# -.net
KiCad netlist of a schematic drawn in Altium Designer
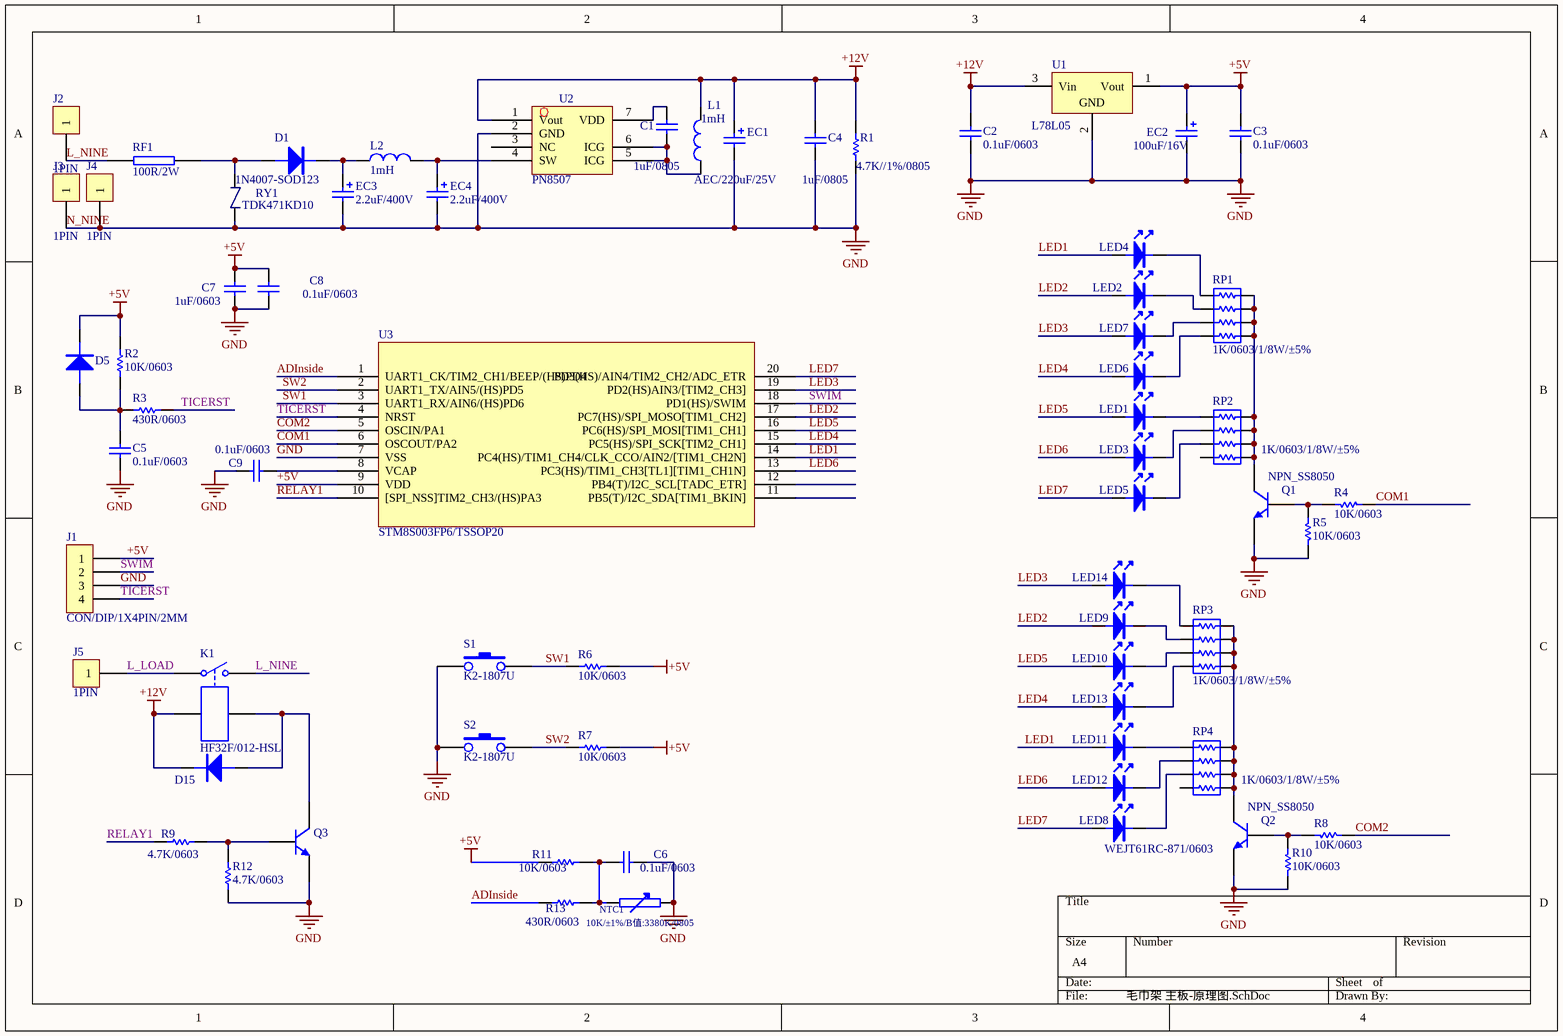
[diagram p0: 毛巾架 主板-原理图.SchDoc]

(export (version "E")
  (design (tool "Eeschema 10.0.6"))
  (components
    (comp (ref "C1")
      (value "1uF/0805")
      (footprint "CAP/SMT/0805C")
      (libsource (lib "Menred_原理图 封装库") (part "CAP/CAP/SMT/0805C"))
    )
    (comp (ref "C2")
      (value "0.1uF/0603")
      (footprint "CAP/SMT/0603C")
      (libsource (lib "Menred_原理图 封装库") (part "CAP/CAP/SMT/0603C"))
    )
    (comp (ref "C3")
      (value "0.1uF/0603")
      (footprint "CAP/SMT/0603C")
      (libsource (lib "Menred_原理图 封装库") (part "CAP/CAP/SMT/0603C"))
    )
    (comp (ref "C4")
      (value "1uF/0805")
      (footprint "CAP/SMT/0805C")
      (libsource (lib "Menred_原理图 封装库") (part "CAP/CAP/SMT/0805C"))
    )
    (comp (ref "C5")
      (value "0.1uF/0603")
      (footprint "CAP/SMT/0603C")
      (libsource (lib "Menred_原理图 封装库") (part "CAP/CAP/SMT/0603C"))
    )
    (comp (ref "C6")
      (value "0.1uF/0603")
      (footprint "CAP/SMT/0603C")
      (libsource (lib "Menred_原理图 封装库") (part "CAP/CAP/SMT/0603C"))
    )
    (comp (ref "C7")
      (value "1uF/0603")
      (footprint "CAP/SMT/0603C")
      (libsource (lib "Menred_原理图 封装库") (part "CAP/CAP/SMT/0603C"))
    )
    (comp (ref "C8")
      (value "0.1uF/0603")
      (footprint "CAP/SMT/0603C")
      (libsource (lib "Menred_原理图 封装库") (part "CAP/CAP/SMT/0603C"))
    )
    (comp (ref "C9")
      (value "0.1uF/0603")
      (footprint "CAP/SMT/0603C")
      (libsource (lib "Menred_原理图 封装库") (part "CAP/CAP/SMT/0603C"))
    )
    (comp (ref "D1")
      (value "1N4007-SOD123")
      (footprint "D/SMT/SOD123")
      (libsource (lib "二极管类器件") (part "D/D/SMT/1N4007-SOD123"))
    )
    (comp (ref "D5")
      (value "1N4148/SOD-123")
      (footprint "D/SMT/SOD-123")
      (description "VR=75V T(-65-175)P(0.5W)VF=0.6V")
      (libsource (lib "Menred_原理图 封装库") (part "D/D/SMT/1N4148/SOD-123"))
    )
    (comp (ref "D15")
      (value "1N4148/SOD-123")
      (footprint "D/SMT/SOD-123")
      (description "VR=75V T(-65-175)P(0.5W)VF=0.6V")
      (libsource (lib "Menred_原理图 封装库") (part "D/D/SMT/1N4148/SOD-123"))
    )
    (comp (ref "EC1")
      (value "AEC/220uF/25V")
      (footprint "CAP/DIP/330UF/25V")
      (libsource (lib "Menred_原理图 封装库") (part "CAP/AEC/DIP/330uF/25V"))
    )
    (comp (ref "EC2")
      (value "100uF/16V")
      (footprint "CAP/SMT/47uF/16V")
      (libsource (lib "Menred_原理图 封装库") (part "CAP/AEC/SMT/47uF/16V"))
    )
    (comp (ref "EC3")
      (value "2.2uF/400V")
      (footprint "CAP/DIP/2.2UF/400V/2.5mm")
      (libsource (lib "Menred_原理图 封装库") (part "CAP/AEC/DIP/2.2uF/400V"))
    )
    (comp (ref "EC4")
      (value "2.2uF/400V")
      (footprint "CAP/DIP/2.2UF/400V/2.5mm")
      (libsource (lib "Menred_原理图 封装库") (part "CAP/AEC/DIP/2.2uF/400V"))
    )
    (comp (ref "J1")
      (value "CON/DIP/1X4PIN/2MM")
      (footprint "CON/DIP/1×4PIN/2.0MM")
      (description "Connector")
      (libsource (lib "Menred_原理图 封装库") (part "CON/DIP/1X4PIN/2MM"))
    )
    (comp (ref "J2")
      (value "1PIN")
      (footprint "CON/DIP/1PIN")
      (description "Connector")
      (libsource (lib "Menred_原理图 封装库") (part "CON/DIP/1PIN"))
    )
    (comp (ref "J3")
      (value "1PIN")
      (footprint "CON/DIP/1PIN")
      (description "Connector")
      (libsource (lib "Menred_原理图 封装库") (part "CON/DIP/1PIN"))
    )
    (comp (ref "J4")
      (value "1PIN")
      (footprint "CON/DIP/1PIN")
      (description "Connector")
      (libsource (lib "Menred_原理图 封装库") (part "CON/DIP/1PIN"))
    )
    (comp (ref "J5")
      (value "1PIN")
      (footprint "CON/DIP/1PIN")
      (description "Connector")
      (libsource (lib "") (part "CON/DIP/1PIN_1"))
    )
    (comp (ref "K1")
      (value "HF32F/012-HSL")
      (footprint "RELAY/HF32F-012-HSL")
      (libsource (lib "Menred_原理图 封装库") (part "RELAY/GENERAL/DIP/HF32F/012-HSL"))
    )
    (comp (ref "L1")
      (value "1mH")
      (footprint "L/DIP/1mH")
      (description "工字电感")
      (libsource (lib "Menred_原理图 封装库") (part "L/L/DIP/JYGX68-1.0mH/300mA"))
    )
    (comp (ref "L2")
      (value "1mH")
      (footprint "L/DIP/1mH")
      (description "工字电感")
      (libsource (lib "Menred_原理图 封装库") (part "L/L/DIP/JYGX68-1.0mH/300mA"))
    )
    (comp (ref "LED1")
      (value "WEJT61RC-871/0603")
      (footprint "D/SMT/LED/0603")
      (libsource (lib "Menred_原理图 封装库") (part "D/LED/SMT/WEJT61RC-871/0603"))
    )
    (comp (ref "LED2")
      (value "WEJT61RC-871/0603")
      (footprint "D/SMT/LED/0603")
      (libsource (lib "Menred_原理图 封装库") (part "D/LED/SMT/WEJT61RC-871/0603"))
    )
    (comp (ref "LED3")
      (value "WEJT61RC-871/0603")
      (footprint "D/SMT/LED/0603")
      (libsource (lib "Menred_原理图 封装库") (part "D/LED/SMT/WEJT61RC-871/0603"))
    )
    (comp (ref "LED4")
      (value "WEJT61RC-871/0603")
      (footprint "D/SMT/LED/0603")
      (libsource (lib "Menred_原理图 封装库") (part "D/LED/SMT/WEJT61RC-871/0603"))
    )
    (comp (ref "LED5")
      (value "WEJT61RC-871/0603")
      (footprint "D/SMT/LED/0603")
      (libsource (lib "Menred_原理图 封装库") (part "D/LED/SMT/WEJT61RC-871/0603"))
    )
    (comp (ref "LED6")
      (value "WEJT61RC-871/0603")
      (footprint "D/SMT/LED/0603")
      (libsource (lib "Menred_原理图 封装库") (part "D/LED/SMT/WEJT61RC-871/0603"))
    )
    (comp (ref "LED7")
      (value "WEJT61RC-871/0603")
      (footprint "D/SMT/LED/0603")
      (libsource (lib "Menred_原理图 封装库") (part "D/LED/SMT/WEJT61RC-871/0603"))
    )
    (comp (ref "LED8")
      (value "WEJT61RC-871/0603")
      (footprint "D/SMT/LED/0603")
      (libsource (lib "Menred_原理图 封装库") (part "D/LED/SMT/WEJT61RC-871/0603"))
    )
    (comp (ref "LED9")
      (value "WEJT61RC-871/0603")
      (footprint "D/SMT/LED/0603")
      (libsource (lib "Menred_原理图 封装库") (part "D/LED/SMT/WEJT61RC-871/0603"))
    )
    (comp (ref "LED10")
      (value "WEJT61RC-871/0603")
      (footprint "D/SMT/LED/0603")
      (libsource (lib "Menred_原理图 封装库") (part "D/LED/SMT/WEJT61RC-871/0603"))
    )
    (comp (ref "LED11")
      (value "WEJT61RC-871/0603")
      (footprint "D/SMT/LED/0603")
      (libsource (lib "Menred_原理图 封装库") (part "D/LED/SMT/WEJT61RC-871/0603"))
    )
    (comp (ref "LED12")
      (value "WEJT61RC-871/0603")
      (footprint "D/SMT/LED/0603")
      (libsource (lib "Menred_原理图 封装库") (part "D/LED/SMT/WEJT61RC-871/0603"))
    )
    (comp (ref "LED13")
      (value "WEJT61RC-871/0603")
      (footprint "D/SMT/LED/0603")
      (libsource (lib "Menred_原理图 封装库") (part "D/LED/SMT/WEJT61RC-871/0603"))
    )
    (comp (ref "LED14")
      (value "WEJT61RC-871/0603")
      (footprint "D/SMT/LED/0603")
      (libsource (lib "Menred_原理图 封装库") (part "D/LED/SMT/WEJT61RC-871/0603"))
    )
    (comp (ref "NTC1")
      (value "10K/±1%/B值:3380K/0805")
      (footprint "Sensor/S_NTC_DIP")
      (description "3380(10K)")
      (libsource (lib "Menred_原理图 封装库") (part "SENSOR/NTC_SMD"))
    )
    (comp (ref "Q1")
      (value "NPN_SS8050")
      (footprint "BJT/SMT/SOT-23")
      (description "Vce25V/Vcb40V/Veb5V/Ic1.5V/Pd300mW")
      (fields (field (name "PUBLISHER") "*"))
      (libsource (lib "Menred_原理图 封装库") (part "BJT/NPN/SMT/SS8050/SOT-23"))
    )
    (comp (ref "Q2")
      (value "NPN_SS8050")
      (footprint "BJT/SMT/SOT-23")
      (description "Vce25V/Vcb40V/Veb5V/Ic1.5V/Pd300mW")
      (fields (field (name "PUBLISHER") "*"))
      (libsource (lib "Menred_原理图 封装库") (part "BJT/NPN/SMT/SS8050/SOT-23"))
    )
    (comp (ref "Q3")
      (value "NPN_SS8050")
      (footprint "BJT/SMT/SOT-23")
      (fields (field (name "PUBLISHER") "*"))
      (libsource (lib "Menred_原理图 封装库") (part "BJT/NPN/SMT/SS8050/SOT-23"))
    )
    (comp (ref "R1")
      (value "4.7K//1%/0805")
      (footprint "0805R")
      (libsource (lib "Menred_原理图 封装库") (part "RES/RES/SMT/0805"))
    )
    (comp (ref "R2")
      (value "10K/0603")
      (footprint "0603R")
      (libsource (lib "Menred_原理图 封装库") (part "RES/RES/SMT/0603"))
    )
    (comp (ref "R3")
      (value "430R/0603")
      (footprint "0603R")
      (libsource (lib "Menred_原理图 封装库") (part "RES/RES/SMT/0603"))
    )
    (comp (ref "R4")
      (value "10K/0603")
      (footprint "0603R")
      (libsource (lib "Menred_原理图 封装库") (part "RES/RES/SMT/0603"))
    )
    (comp (ref "R5")
      (value "10K/0603")
      (footprint "0603R")
      (libsource (lib "Menred_原理图 封装库") (part "RES/RES/SMT/0603"))
    )
    (comp (ref "R6")
      (value "10K/0603")
      (footprint "0603R")
      (libsource (lib "Menred_原理图 封装库") (part "RES/RES/SMT/0603"))
    )
    (comp (ref "R7")
      (value "10K/0603")
      (footprint "0603R")
      (libsource (lib "Menred_原理图 封装库") (part "RES/RES/SMT/0603"))
    )
    (comp (ref "R8")
      (value "10K/0603")
      (footprint "0603R")
      (libsource (lib "Menred_原理图 封装库") (part "RES/RES/SMT/0603"))
    )
    (comp (ref "R9")
      (value "4.7K/0603")
      (footprint "0603R")
      (libsource (lib "Menred_原理图 封装库") (part "RES/RES/SMT/0603"))
    )
    (comp (ref "R10")
      (value "10K/0603")
      (footprint "0603R")
      (libsource (lib "Menred_原理图 封装库") (part "RES/RES/SMT/0603"))
    )
    (comp (ref "R11")
      (value "10K/0603")
      (footprint "0603R")
      (libsource (lib "Menred_原理图 封装库") (part "RES/RES/SMT/0603"))
    )
    (comp (ref "R12")
      (value "4.7K/0603")
      (footprint "0603R")
      (libsource (lib "Menred_原理图 封装库") (part "RES/RES/SMT/0603"))
    )
    (comp (ref "R13")
      (value "430R/0603")
      (footprint "0603R")
      (libsource (lib "Menred_原理图 封装库") (part "RES/RES/SMT/0603"))
    )
    (comp (ref "RF1")
      (value "100R/2W")
      (footprint "FUSE/3.15A")
      (libsource (lib "Menred_原理图 封装库") (part "FUSE/FUSE/DIP/3.15A"))
    )
    (comp (ref "RP1")
      (value "1K/0603/1/8W/±5%")
      (footprint "0603R*4")
      (description "Isolated Resistor Network")
      (fields (field (name "PUBLISHER") "Altium Limited"))
      (libsource (lib "Menred_原理图 封装库") (part "RES /PACKS/SMT/0603*4"))
    )
    (comp (ref "RP2")
      (value "1K/0603/1/8W/±5%")
      (footprint "0603R*4")
      (description "Isolated Resistor Network")
      (fields (field (name "PUBLISHER") "Altium Limited"))
      (libsource (lib "Menred_原理图 封装库") (part "RES /PACKS/SMT/0603*4"))
    )
    (comp (ref "RP3")
      (value "1K/0603/1/8W/±5%")
      (footprint "0603R*4")
      (description "Isolated Resistor Network")
      (fields (field (name "PUBLISHER") "Altium Limited"))
      (libsource (lib "Menred_原理图 封装库") (part "RES /PACKS/SMT/0603*4"))
    )
    (comp (ref "RP4")
      (value "1K/0603/1/8W/±5%")
      (footprint "0603R*4")
      (description "Isolated Resistor Network")
      (fields (field (name "PUBLISHER") "Altium Limited"))
      (libsource (lib "Menred_原理图 封装库") (part "RES /PACKS/SMT/0603*4"))
    )
    (comp (ref "RY1")
      (value "TDK471KD10")
      (footprint "RES/RY/TDK471KD10")
      (libsource (lib "Menred_原理图 封装库") (part "RES/RY/DIP/TDK471KD10"))
    )
    (comp (ref "S1")
      (value "K2-1807U")
      (footprint "SWITCH/K2-1807U")
      (libsource (lib "Menred_原理图 封装库") (part "SWITCH/SMT/K2-1807U"))
    )
    (comp (ref "S2")
      (value "K2-1807U")
      (footprint "SWITCH/K2-1807U")
      (libsource (lib "Menred_原理图 封装库") (part "SWITCH/SMT/K2-1807U"))
    )
    (comp (ref "U1")
      (value "L78L05")
      (footprint "SOT-89-3L(78L05)")
      (description "5V三端稳压器 output imax 0.1A")
      (fields (field (name "MANUFACTURER") "Generic Components"))
      (libsource (lib "Menred_原理图 封装库") (part "IC/POWER/SMT/L78L05/SOT-89"))
    )
    (comp (ref "U2")
      (value "PN8507")
      (footprint "SOP-7")
      (libsource (lib "集成芯片类") (part "IC/POWER/SMT/PN8507/SOP-8"))
    )
    (comp (ref "U3")
      (value "STM8S003FP6/TSSOP20")
      (footprint "TSSOP20")
      (libsource (lib "Menred_原理图 封装库") (part "MCU/SMT/STM8S003FP6/TSSOP20"))
    )
  )
  (nets
    (net (code "1") (name "+5V") (class "Default")
      (node (ref "C3") (pin "2") (pinfunction "2_2") (pintype "passive"))
      (node (ref "C7") (pin "2") (pinfunction "2_2") (pintype "passive"))
      (node (ref "C8") (pin "2") (pinfunction "2_2") (pintype "passive"))
      (node (ref "D5") (pin "1") (pinfunction "K_1") (pintype "passive"))
      (node (ref "EC2") (pin "1") (pinfunction "1_1") (pintype "passive"))
      (node (ref "J1") (pin "1") (pinfunction "1_1") (pintype "passive"))
      (node (ref "R11") (pin "2") (pinfunction "2_2") (pintype "passive"))
      (node (ref "R2") (pin "1") (pinfunction "1_1") (pintype "passive"))
      (node (ref "R6") (pin "2") (pinfunction "2_2") (pintype "passive"))
      (node (ref "R7") (pin "2") (pinfunction "2_2") (pintype "passive"))
      (node (ref "U1") (pin "1") (pinfunction "Vout_1") (pintype "passive"))
      (node (ref "U3") (pin "9") (pinfunction "VDD_9") (pintype "power_in"))
    )
    (net (code "2") (name "+12V") (class "Default")
      (node (ref "C2") (pin "2") (pinfunction "2_2") (pintype "passive"))
      (node (ref "C4") (pin "2") (pinfunction "2_2") (pintype "passive"))
      (node (ref "D15") (pin "1") (pinfunction "K_1") (pintype "passive"))
      (node (ref "EC1") (pin "1") (pinfunction "1_1") (pintype "passive"))
      (node (ref "K1") (pin "3") (pinfunction "3_3") (pintype "passive"))
      (node (ref "L1") (pin "2") (pinfunction "2_2") (pintype "passive"))
      (node (ref "R1") (pin "2") (pinfunction "2_2") (pintype "passive"))
      (node (ref "U1") (pin "3") (pinfunction "Vin_3") (pintype "passive"))
      (node (ref "U2") (pin "1") (pinfunction "Vout_1") (pintype "passive"))
    )
    (net (code "3") (name "/ADInside") (class "Default")
      (node (ref "R13") (pin "2") (pinfunction "2_2") (pintype "passive"))
      (node (ref "U3") (pin "1") (pinfunction "UART1_CK/TIM2_CH1/BEEP/(HS)PD4_1") (pintype "power_in"))
    )
    (net (code "4") (name "/COM1") (class "Default")
      (node (ref "R4") (pin "1") (pinfunction "1_1") (pintype "passive"))
      (node (ref "U3") (pin "6") (pinfunction "OSCOUT/PA2_6") (pintype "power_in"))
    )
    (net (code "5") (name "/COM2") (class "Default")
      (node (ref "R8") (pin "1") (pinfunction "1_1") (pintype "passive"))
      (node (ref "U3") (pin "5") (pinfunction "OSCIN/PA1_5") (pintype "power_in"))
    )
    (net (code "6") (name "/LED1") (class "Default")
      (node (ref "LED11") (pin "2") (pinfunction "A_2") (pintype "passive"))
      (node (ref "LED4") (pin "2") (pinfunction "A_2") (pintype "passive"))
      (node (ref "U3") (pin "14") (pinfunction "PC4(HS)/TIM1_CH4/CLK_CCO/AIN2/[TIM1_CH2N]_14") (pintype "power_in"))
    )
    (net (code "7") (name "/LED2") (class "Default")
      (node (ref "LED2") (pin "2") (pinfunction "A_2") (pintype "passive"))
      (node (ref "LED9") (pin "2") (pinfunction "A_2") (pintype "passive"))
      (node (ref "U3") (pin "17") (pinfunction "PC7(HS)/SPI_MOSO[TIM1_CH2]_17") (pintype "power_in"))
    )
    (net (code "8") (name "/LED3") (class "Default")
      (node (ref "LED14") (pin "2") (pinfunction "A_2") (pintype "passive"))
      (node (ref "LED7") (pin "2") (pinfunction "A_2") (pintype "passive"))
      (node (ref "U3") (pin "19") (pinfunction "PD2(HS)AIN3/[TIM2_CH3]_19") (pintype "power_in"))
    )
    (net (code "9") (name "/LED4") (class "Default")
      (node (ref "LED13") (pin "2") (pinfunction "A_2") (pintype "passive"))
      (node (ref "LED6") (pin "2") (pinfunction "A_2") (pintype "passive"))
      (node (ref "U3") (pin "15") (pinfunction "PC5(HS)/SPI_SCK[TIM2_CH1]_15") (pintype "power_in"))
    )
    (net (code "10") (name "/LED5") (class "Default")
      (node (ref "LED1") (pin "2") (pinfunction "A_2") (pintype "passive"))
      (node (ref "LED10") (pin "2") (pinfunction "A_2") (pintype "passive"))
      (node (ref "U3") (pin "16") (pinfunction "PC6(HS)/SPI_MOSI[TIM1_CH1]_16") (pintype "power_in"))
    )
    (net (code "11") (name "/LED6") (class "Default")
      (node (ref "LED12") (pin "2") (pinfunction "A_2") (pintype "passive"))
      (node (ref "LED3") (pin "2") (pinfunction "A_2") (pintype "passive"))
      (node (ref "U3") (pin "13") (pinfunction "PC3(HS)/TIM1_CH3[TL1][TIM1_CH1N]_13") (pintype "power_in"))
    )
    (net (code "12") (name "/LED7") (class "Default")
      (node (ref "LED5") (pin "2") (pinfunction "A_2") (pintype "passive"))
      (node (ref "LED8") (pin "2") (pinfunction "A_2") (pintype "passive"))
      (node (ref "U3") (pin "20") (pinfunction "PD3(HS)/AIN4/TIM2_CH2/ADC_ETR_20") (pintype "power_in"))
    )
    (net (code "13") (name "/L_LOAD") (class "Default")
      (node (ref "J5") (pin "1") (pinfunction "1_1") (pintype "passive"))
      (node (ref "K1") (pin "1") (pinfunction "1_1") (pintype "passive"))
    )
    (net (code "14") (name "/L_NINE") (class "Default")
      (node (ref "J2") (pin "1") (pinfunction "1_1") (pintype "passive"))
      (node (ref "K1") (pin "2") (pinfunction "2_2") (pintype "passive"))
      (node (ref "RF1") (pin "2") (pinfunction "2_2") (pintype "passive"))
    )
    (net (code "15") (name "/RELAY1") (class "Default")
      (node (ref "R9") (pin "2") (pinfunction "2_2") (pintype "passive"))
      (node (ref "U3") (pin "10") (pinfunction "[SPI_NSS]TIM2_CH3/(HS)PA3_10") (pintype "power_in"))
    )
    (net (code "16") (name "/SW1") (class "Default")
      (node (ref "R6") (pin "1") (pinfunction "1_1") (pintype "passive"))
      (node (ref "S1") (pin "2") (pinfunction "2_2") (pintype "passive"))
      (node (ref "U3") (pin "3") (pinfunction "UART1_RX/AIN6/(HS)PD6_3") (pintype "power_in"))
    )
    (net (code "17") (name "/SW2") (class "Default")
      (node (ref "R7") (pin "1") (pinfunction "1_1") (pintype "passive"))
      (node (ref "S2") (pin "2") (pinfunction "2_2") (pintype "passive"))
      (node (ref "U3") (pin "2") (pinfunction "UART1_TX/AIN5/(HS)PD5_2") (pintype "power_in"))
    )
    (net (code "18") (name "/SWIM") (class "Default")
      (node (ref "J1") (pin "2") (pinfunction "2_2") (pintype "passive"))
      (node (ref "U3") (pin "18") (pinfunction "PD1(HS)/SWIM_18") (pintype "power_in"))
    )
    (net (code "19") (name "/TICERST") (class "Default")
      (node (ref "J1") (pin "4") (pinfunction "4_4") (pintype "passive"))
      (node (ref "R3") (pin "2") (pinfunction "2_2") (pintype "passive"))
      (node (ref "U3") (pin "4") (pinfunction "NRST_4") (pintype "power_in"))
    )
    (net (code "20") (name "GND") (class "Default")
      (node (ref "C2") (pin "1") (pinfunction "1_1") (pintype "passive"))
      (node (ref "C3") (pin "1") (pinfunction "1_1") (pintype "passive"))
      (node (ref "C4") (pin "1") (pinfunction "1_1") (pintype "passive"))
      (node (ref "C5") (pin "2") (pinfunction "2_2") (pintype "passive"))
      (node (ref "C6") (pin "1") (pinfunction "1_1") (pintype "passive"))
      (node (ref "C7") (pin "1") (pinfunction "1_1") (pintype "passive"))
      (node (ref "C8") (pin "1") (pinfunction "1_1") (pintype "passive"))
      (node (ref "C9") (pin "2") (pinfunction "2_2") (pintype "passive"))
      (node (ref "EC1") (pin "2") (pinfunction "2_2") (pintype "passive"))
      (node (ref "EC2") (pin "2") (pinfunction "2_2") (pintype "passive"))
      (node (ref "EC3") (pin "2") (pinfunction "2_2") (pintype "passive"))
      (node (ref "EC4") (pin "2") (pinfunction "2_2") (pintype "passive"))
      (node (ref "J1") (pin "3") (pinfunction "3_3") (pintype "passive"))
      (node (ref "J3") (pin "1") (pinfunction "1_1") (pintype "passive"))
      (node (ref "J4") (pin "1") (pinfunction "1_1") (pintype "passive"))
      (node (ref "NTC1") (pin "2") (pinfunction "2_2") (pintype "passive"))
      (node (ref "Q1") (pin "2") (pinfunction "E_2") (pintype "passive"))
      (node (ref "Q2") (pin "2") (pinfunction "E_2") (pintype "passive"))
      (node (ref "Q3") (pin "2") (pinfunction "E_2") (pintype "passive"))
      (node (ref "R1") (pin "1") (pinfunction "1_1") (pintype "passive"))
      (node (ref "R10") (pin "2") (pinfunction "2_2") (pintype "passive"))
      (node (ref "R12") (pin "2") (pinfunction "2_2") (pintype "passive"))
      (node (ref "R5") (pin "2") (pinfunction "2_2") (pintype "passive"))
      (node (ref "RY1") (pin "1") (pinfunction "1_1") (pintype "passive"))
      (node (ref "S1") (pin "1") (pinfunction "1_1") (pintype "passive"))
      (node (ref "S2") (pin "1") (pinfunction "1_1") (pintype "passive"))
      (node (ref "U1") (pin "2") (pinfunction "GND_2") (pintype "passive"))
      (node (ref "U2") (pin "2") (pinfunction "GND_2") (pintype "passive"))
      (node (ref "U3") (pin "7") (pinfunction "VSS_7") (pintype "power_in"))
    )
    (net (code "21") (name "Net-(C1-Pad1)") (class "Default")
      (node (ref "C1") (pin "1") (pinfunction "1_1") (pintype "passive"))
      (node (ref "L1") (pin "1") (pinfunction "1_1") (pintype "passive"))
      (node (ref "U2") (pin "5") (pinfunction "ICG_5") (pintype "passive"))
      (node (ref "U2") (pin "6") (pinfunction "ICG_6") (pintype "passive"))
    )
    (net (code "22") (name "Net-(C6-Pad2)") (class "Default")
      (node (ref "C6") (pin "2") (pinfunction "2_2") (pintype "passive"))
      (node (ref "NTC1") (pin "1") (pinfunction "1_1") (pintype "passive"))
      (node (ref "R11") (pin "1") (pinfunction "1_1") (pintype "passive"))
      (node (ref "R13") (pin "1") (pinfunction "1_1") (pintype "passive"))
    )
    (net (code "23") (name "Net-(D1-A)") (class "Default")
      (node (ref "D1") (pin "2") (pinfunction "A_2") (pintype "passive"))
      (node (ref "RF1") (pin "1") (pinfunction "1_1") (pintype "passive"))
      (node (ref "RY1") (pin "2") (pinfunction "2_2") (pintype "passive"))
    )
    (net (code "24") (name "Net-(D1-K)") (class "Default")
      (node (ref "D1") (pin "1") (pinfunction "K_1") (pintype "passive"))
      (node (ref "EC3") (pin "1") (pinfunction "1_1") (pintype "passive"))
      (node (ref "L2") (pin "1") (pinfunction "1_1") (pintype "passive"))
    )
    (net (code "25") (name "Net-(D5-A)") (class "Default")
      (node (ref "C5") (pin "1") (pinfunction "1_1") (pintype "passive"))
      (node (ref "D5") (pin "2") (pinfunction "A_2") (pintype "passive"))
      (node (ref "R2") (pin "2") (pinfunction "2_2") (pintype "passive"))
      (node (ref "R3") (pin "1") (pinfunction "1_1") (pintype "passive"))
    )
    (net (code "26") (name "Net-(D15-A)") (class "Default")
      (node (ref "D15") (pin "2") (pinfunction "A_2") (pintype "passive"))
      (node (ref "K1") (pin "4") (pinfunction "4_4") (pintype "passive"))
      (node (ref "Q3") (pin "3") (pinfunction "C_3") (pintype "passive"))
    )
    (net (code "27") (name "Net-(LED1-K)") (class "Default")
      (node (ref "LED1") (pin "1") (pinfunction "K_1") (pintype "passive"))
      (node (ref "RP2") (pin "5") (pinfunction "5_5") (pintype "passive"))
    )
    (net (code "28") (name "Net-(LED2-K)") (class "Default")
      (node (ref "LED2") (pin "1") (pinfunction "K_1") (pintype "passive"))
      (node (ref "RP1") (pin "6") (pinfunction "6_6") (pintype "passive"))
    )
    (net (code "29") (name "Net-(LED3-K)") (class "Default")
      (node (ref "LED3") (pin "1") (pinfunction "K_1") (pintype "passive"))
      (node (ref "RP2") (pin "6") (pinfunction "6_6") (pintype "passive"))
    )
    (net (code "30") (name "Net-(LED4-K)") (class "Default")
      (node (ref "LED4") (pin "1") (pinfunction "K_1") (pintype "passive"))
      (node (ref "RP1") (pin "5") (pinfunction "5_5") (pintype "passive"))
    )
    (net (code "31") (name "Net-(LED5-K)") (class "Default")
      (node (ref "LED5") (pin "1") (pinfunction "K_1") (pintype "passive"))
      (node (ref "RP2") (pin "7") (pinfunction "7_7") (pintype "passive"))
    )
    (net (code "32") (name "Net-(LED6-K)") (class "Default")
      (node (ref "LED6") (pin "1") (pinfunction "K_1") (pintype "passive"))
      (node (ref "RP1") (pin "8") (pinfunction "8_8") (pintype "passive"))
    )
    (net (code "33") (name "Net-(LED7-K)") (class "Default")
      (node (ref "LED7") (pin "1") (pinfunction "K_1") (pintype "passive"))
      (node (ref "RP1") (pin "7") (pinfunction "7_7") (pintype "passive"))
    )
    (net (code "34") (name "Net-(LED8-K)") (class "Default")
      (node (ref "LED8") (pin "1") (pinfunction "K_1") (pintype "passive"))
      (node (ref "RP4") (pin "7") (pinfunction "7_7") (pintype "passive"))
    )
    (net (code "35") (name "Net-(LED9-K)") (class "Default")
      (node (ref "LED9") (pin "1") (pinfunction "K_1") (pintype "passive"))
      (node (ref "RP3") (pin "6") (pinfunction "6_6") (pintype "passive"))
    )
    (net (code "36") (name "Net-(LED10-K)") (class "Default")
      (node (ref "LED10") (pin "1") (pinfunction "K_1") (pintype "passive"))
      (node (ref "RP3") (pin "7") (pinfunction "7_7") (pintype "passive"))
    )
    (net (code "37") (name "Net-(LED11-K)") (class "Default")
      (node (ref "LED11") (pin "1") (pinfunction "K_1") (pintype "passive"))
      (node (ref "RP4") (pin "5") (pinfunction "5_5") (pintype "passive"))
    )
    (net (code "38") (name "Net-(LED12-K)") (class "Default")
      (node (ref "LED12") (pin "1") (pinfunction "K_1") (pintype "passive"))
      (node (ref "RP4") (pin "6") (pinfunction "6_6") (pintype "passive"))
    )
    (net (code "39") (name "Net-(LED13-K)") (class "Default")
      (node (ref "LED13") (pin "1") (pinfunction "K_1") (pintype "passive"))
      (node (ref "RP3") (pin "8") (pinfunction "8_8") (pintype "passive"))
    )
    (net (code "40") (name "Net-(LED14-K)") (class "Default")
      (node (ref "LED14") (pin "1") (pinfunction "K_1") (pintype "passive"))
      (node (ref "RP3") (pin "5") (pinfunction "5_5") (pintype "passive"))
    )
    (net (code "41") (name "Net-(Q1-B)") (class "Default")
      (node (ref "Q1") (pin "1") (pinfunction "B_1") (pintype "passive"))
      (node (ref "R4") (pin "2") (pinfunction "2_2") (pintype "passive"))
      (node (ref "R5") (pin "1") (pinfunction "1_1") (pintype "passive"))
    )
    (net (code "42") (name "Net-(Q1-C)") (class "Default")
      (node (ref "Q1") (pin "3") (pinfunction "C_3") (pintype "passive"))
      (node (ref "RP1") (pin "1") (pinfunction "1_1") (pintype "passive"))
      (node (ref "RP1") (pin "2") (pinfunction "2_2") (pintype "passive"))
      (node (ref "RP1") (pin "3") (pinfunction "3_3") (pintype "passive"))
      (node (ref "RP1") (pin "4") (pinfunction "4_4") (pintype "passive"))
      (node (ref "RP2") (pin "1") (pinfunction "1_1") (pintype "passive"))
      (node (ref "RP2") (pin "2") (pinfunction "2_2") (pintype "passive"))
      (node (ref "RP2") (pin "3") (pinfunction "3_3") (pintype "passive"))
      (node (ref "RP2") (pin "4") (pinfunction "4_4") (pintype "passive"))
    )
    (net (code "43") (name "Net-(Q2-B)") (class "Default")
      (node (ref "Q2") (pin "1") (pinfunction "B_1") (pintype "passive"))
      (node (ref "R10") (pin "1") (pinfunction "1_1") (pintype "passive"))
      (node (ref "R8") (pin "2") (pinfunction "2_2") (pintype "passive"))
    )
    (net (code "44") (name "Net-(Q2-C)") (class "Default")
      (node (ref "Q2") (pin "3") (pinfunction "C_3") (pintype "passive"))
      (node (ref "RP3") (pin "1") (pinfunction "1_1") (pintype "passive"))
      (node (ref "RP3") (pin "2") (pinfunction "2_2") (pintype "passive"))
      (node (ref "RP3") (pin "3") (pinfunction "3_3") (pintype "passive"))
      (node (ref "RP3") (pin "4") (pinfunction "4_4") (pintype "passive"))
      (node (ref "RP4") (pin "1") (pinfunction "1_1") (pintype "passive"))
      (node (ref "RP4") (pin "2") (pinfunction "2_2") (pintype "passive"))
      (node (ref "RP4") (pin "3") (pinfunction "3_3") (pintype "passive"))
      (node (ref "RP4") (pin "4") (pinfunction "4_4") (pintype "passive"))
    )
    (net (code "45") (name "Net-(Q3-B)") (class "Default")
      (node (ref "Q3") (pin "1") (pinfunction "B_1") (pintype "passive"))
      (node (ref "R12") (pin "1") (pinfunction "1_1") (pintype "passive"))
      (node (ref "R9") (pin "1") (pinfunction "1_1") (pintype "passive"))
    )
    (net (code "46") (name "Net-(U2-SW)") (class "Default")
      (node (ref "EC4") (pin "1") (pinfunction "1_1") (pintype "passive"))
      (node (ref "L2") (pin "2") (pinfunction "2_2") (pintype "passive"))
      (node (ref "U2") (pin "4") (pinfunction "SW_4") (pintype "passive"))
    )
    (net (code "47") (name "Net-(U2-VDD)") (class "Default")
      (node (ref "C1") (pin "2") (pinfunction "2_2") (pintype "passive"))
      (node (ref "U2") (pin "7") (pinfunction "VDD_7") (pintype "passive"))
    )
    (net (code "48") (name "Net-(U3-VCAP)") (class "Default")
      (node (ref "C9") (pin "1") (pinfunction "1_1") (pintype "passive"))
      (node (ref "U3") (pin "8") (pinfunction "VCAP_8") (pintype "power_in"))
    )
    (net (code "49") (name "unconnected-(RP2-Pad8)") (class "Default")
      (node (ref "RP2") (pin "8") (pinfunction "8_8") (pintype "passive"))
    )
    (net (code "50") (name "unconnected-(RP4-Pad8)") (class "Default")
      (node (ref "RP4") (pin "8") (pinfunction "8_8") (pintype "passive"))
    )
    (net (code "51") (name "unconnected-(U2-NC-Pad3)") (class "Default")
      (node (ref "U2") (pin "3") (pinfunction "NC_3") (pintype "passive"))
    )
    (net (code "52") (name "unconnected-(U3-PB4(T){slash}I2C_SCL[TADC_ETR]-Pad12)") (class "Default")
      (node (ref "U3") (pin "12") (pinfunction "PB4(T)/I2C_SCL[TADC_ETR]_12") (pintype "power_in"))
    )
    (net (code "53") (name "unconnected-(U3-PB5(T){slash}I2C_SDA[TIM1_BKIN]-Pad11)") (class "Default")
      (node (ref "U3") (pin "11") (pinfunction "PB5(T)/I2C_SDA[TIM1_BKIN]_11") (pintype "power_in"))
    )
  )
)
